# stopwatch.net
KiCad netlist of a schematic drawn in EAGLE
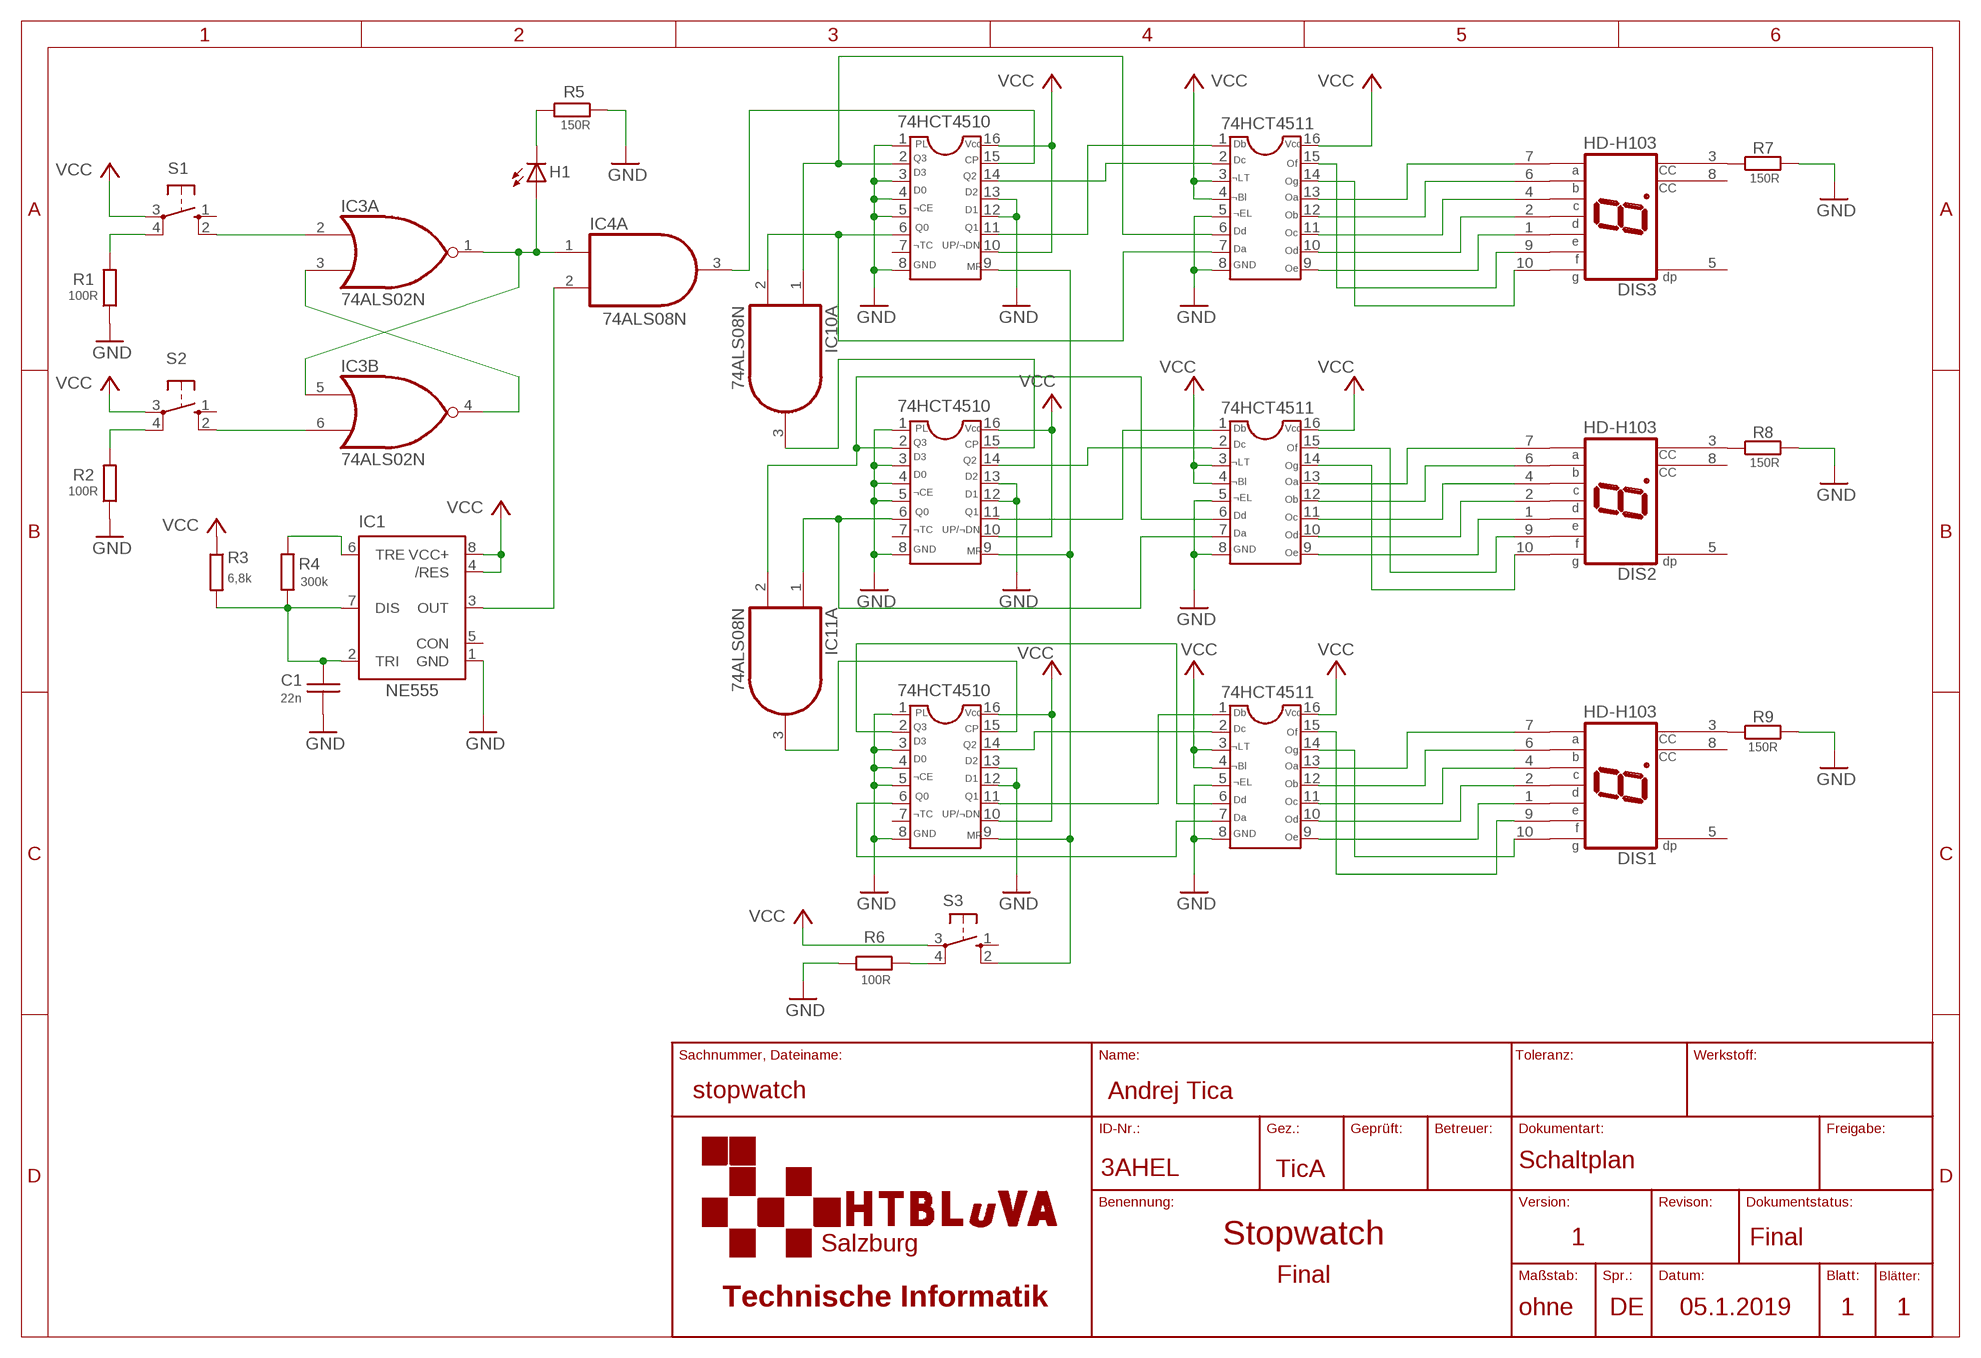
[diagram p0: schematic, sheet 1]

(export (version "E")
  (design (tool "Eeschema 10.0.6"))
  (components
    (comp (ref "C1")
      (value "22n")
      (footprint "eagle-import:C025-025X050")
      (libsource (lib "eagle-import") (part "C-V_025-025X050"))
    )
    (comp (ref "DIS1")
      (value "HD-H103")
      (footprint "eagle-import:HDSP-M")
      (libsource (lib "eagle-import") (part "HD-H103"))
    )
    (comp (ref "DIS2")
      (value "HD-H103")
      (footprint "eagle-import:HDSP-M")
      (libsource (lib "eagle-import") (part "HD-H103"))
    )
    (comp (ref "DIS3")
      (value "HD-H103")
      (footprint "eagle-import:HDSP-M")
      (libsource (lib "eagle-import") (part "HD-H103"))
    )
    (comp (ref "H1")
      (value "LED_10MM")
      (footprint "eagle-import:LED10MM")
      (libsource (lib "eagle-import") (part "LED_10MM"))
    )
    (comp (ref "IC1")
      (value "NE555")
      (footprint "eagle-import:DIL-08")
      (fields (field (name "MF") "Arrow Electronics") (field (name "MPN") "NE555N"))
      (libsource (lib "eagle-import") (part "NE555"))
    )
    (comp (ref "IC2")
      (value "74HCT4510")
      (footprint "eagle-import:DIL16")
      (libsource (lib "eagle-import") (part "ic-logik_TicA_74HCT4510"))
    )
    (comp (ref "IC3")
      (value "74ALS02N")
      (footprint "eagle-import:DIL14")
      (libsource (lib "eagle-import") (part "7402NALS"))
    )
    (comp (ref "IC4")
      (value "74ALS08N")
      (footprint "eagle-import:DIL14")
      (libsource (lib "eagle-import") (part "7408NALS"))
    )
    (comp (ref "IC5")
      (value "74HCT4510")
      (footprint "eagle-import:DIL16")
      (libsource (lib "eagle-import") (part "74HCT4510"))
    )
    (comp (ref "IC6")
      (value "74HCT4510")
      (footprint "eagle-import:DIL16")
      (libsource (lib "eagle-import") (part "ic-logik_TicA_74HCT4510"))
    )
    (comp (ref "IC7")
      (value "74HCT4510")
      (footprint "eagle-import:DIL16")
      (libsource (lib "eagle-import") (part "ic-logik_TicA_74HCT4510"))
    )
    (comp (ref "IC8")
      (value "74HCT4510")
      (footprint "eagle-import:DIL16")
      (libsource (lib "eagle-import") (part "74HCT4510"))
    )
    (comp (ref "IC9")
      (value "74HCT4510")
      (footprint "eagle-import:DIL16")
      (libsource (lib "eagle-import") (part "74HCT4510"))
    )
    (comp (ref "IC10")
      (value "74ALS08N")
      (footprint "eagle-import:DIL14")
      (fields (field (name "SPICEPREFIX") "J"))
      (libsource (lib "eagle-import") (part "7408NALS"))
    )
    (comp (ref "IC11")
      (value "74ALS08N")
      (footprint "eagle-import:DIL14")
      (fields (field (name "SPICEPREFIX") "J"))
      (libsource (lib "eagle-import") (part "7408NALS"))
    )
    (comp (ref "R1")
      (value "100R")
      (footprint "eagle-import:0204_7")
      (libsource (lib "eagle-import") (part "R-H_0204/7"))
    )
    (comp (ref "R2")
      (value "100R")
      (footprint "eagle-import:0204_7")
      (libsource (lib "eagle-import") (part "R-H_0204/7"))
    )
    (comp (ref "R3")
      (value "6,8k")
      (footprint "eagle-import:0204_7")
      (libsource (lib "eagle-import") (part "R-H_0204/7"))
    )
    (comp (ref "R4")
      (value "300k")
      (footprint "eagle-import:0204_7")
      (libsource (lib "eagle-import") (part "R-H_0204/7"))
    )
    (comp (ref "R5")
      (value "150R")
      (footprint "eagle-import:0204_7")
      (libsource (lib "eagle-import") (part "R-H_0204/7"))
    )
    (comp (ref "R6")
      (value "100R")
      (footprint "eagle-import:0204_7")
      (libsource (lib "eagle-import") (part "R-H_0204/7"))
    )
    (comp (ref "R7")
      (value "150R")
      (footprint "eagle-import:0204_7")
      (libsource (lib "eagle-import") (part "R-H_0204/7"))
    )
    (comp (ref "R8")
      (value "150R")
      (footprint "eagle-import:0204_7")
      (libsource (lib "eagle-import") (part "R-H_0204/7"))
    )
    (comp (ref "R9")
      (value "150R")
      (footprint "eagle-import:0204_7")
      (libsource (lib "eagle-import") (part "R-H_0204/7"))
    )
    (comp (ref "S1")
      (value "TASTE10-XX")
      (footprint "eagle-import:VERSTäRKER_B3F-10XX")
      (libsource (lib "eagle-import") (part "TASTE10-XX"))
    )
    (comp (ref "S2")
      (value "TASTE10-XX")
      (footprint "eagle-import:VERSTäRKER_B3F-10XX")
      (libsource (lib "eagle-import") (part "TASTE10-XX"))
    )
    (comp (ref "S3")
      (value "TASTE10-XX")
      (footprint "eagle-import:VERSTäRKER_B3F-10XX")
      (libsource (lib "eagle-import") (part "TASTE10-XX"))
    )
  )
  (nets
    (net (code "1") (name "GND") (class "Default")
      (node (ref "C1") (pin "2") (pinfunction "2_2") (pintype "passive"))
      (node (ref "IC1") (pin "1") (pinfunction "GND_1") (pintype "power_in"))
      (node (ref "IC2") (pin "1") (pinfunction "1_1") (pintype "passive"))
      (node (ref "IC2") (pin "12") (pinfunction "12_12") (pintype "passive"))
      (node (ref "IC2") (pin "13") (pinfunction "13_13") (pintype "passive"))
      (node (ref "IC2") (pin "3") (pinfunction "3_3") (pintype "passive"))
      (node (ref "IC2") (pin "4") (pinfunction "4_4") (pintype "passive"))
      (node (ref "IC2") (pin "5") (pinfunction "5_5") (pintype "passive"))
      (node (ref "IC2") (pin "8") (pinfunction "8_8") (pintype "passive"))
      (node (ref "IC5") (pin "5") (pinfunction "5_5") (pintype "passive"))
      (node (ref "IC5") (pin "8") (pinfunction "8_8") (pintype "passive"))
      (node (ref "IC6") (pin "1") (pinfunction "1_1") (pintype "passive"))
      (node (ref "IC6") (pin "12") (pinfunction "12_12") (pintype "passive"))
      (node (ref "IC6") (pin "13") (pinfunction "13_13") (pintype "passive"))
      (node (ref "IC6") (pin "3") (pinfunction "3_3") (pintype "passive"))
      (node (ref "IC6") (pin "4") (pinfunction "4_4") (pintype "passive"))
      (node (ref "IC6") (pin "5") (pinfunction "5_5") (pintype "passive"))
      (node (ref "IC6") (pin "8") (pinfunction "8_8") (pintype "passive"))
      (node (ref "IC7") (pin "1") (pinfunction "1_1") (pintype "passive"))
      (node (ref "IC7") (pin "12") (pinfunction "12_12") (pintype "passive"))
      (node (ref "IC7") (pin "13") (pinfunction "13_13") (pintype "passive"))
      (node (ref "IC7") (pin "3") (pinfunction "3_3") (pintype "passive"))
      (node (ref "IC7") (pin "4") (pinfunction "4_4") (pintype "passive"))
      (node (ref "IC7") (pin "5") (pinfunction "5_5") (pintype "passive"))
      (node (ref "IC7") (pin "8") (pinfunction "8_8") (pintype "passive"))
      (node (ref "IC8") (pin "5") (pinfunction "5_5") (pintype "passive"))
      (node (ref "IC8") (pin "8") (pinfunction "8_8") (pintype "passive"))
      (node (ref "IC9") (pin "5") (pinfunction "5_5") (pintype "passive"))
      (node (ref "IC9") (pin "8") (pinfunction "8_8") (pintype "passive"))
      (node (ref "R1") (pin "1") (pinfunction "1_1") (pintype "passive"))
      (node (ref "R2") (pin "1") (pinfunction "1_1") (pintype "passive"))
      (node (ref "R5") (pin "1") (pinfunction "1_1") (pintype "passive"))
      (node (ref "R6") (pin "1") (pinfunction "1_1") (pintype "passive"))
      (node (ref "R7") (pin "2") (pinfunction "2_2") (pintype "passive"))
      (node (ref "R8") (pin "2") (pinfunction "2_2") (pintype "passive"))
      (node (ref "R9") (pin "2") (pinfunction "2_2") (pintype "passive"))
    )
    (net (code "2") (name "Net-(DIS1-A)") (class "Default")
      (node (ref "DIS1") (pin "7") (pinfunction "A_7") (pintype "passive"))
      (node (ref "IC9") (pin "13") (pinfunction "13_13") (pintype "passive"))
    )
    (net (code "3") (name "Net-(DIS1-B)") (class "Default")
      (node (ref "DIS1") (pin "6") (pinfunction "B_6") (pintype "passive"))
      (node (ref "IC9") (pin "12") (pinfunction "12_12") (pintype "passive"))
    )
    (net (code "4") (name "Net-(DIS1-C)") (class "Default")
      (node (ref "DIS1") (pin "4") (pinfunction "C_4") (pintype "passive"))
      (node (ref "IC9") (pin "11") (pinfunction "11_11") (pintype "passive"))
    )
    (net (code "5") (name "Net-(DIS1-CC-Pad3)") (class "Default")
      (node (ref "DIS1") (pin "3") (pinfunction "CC_3") (pintype "passive"))
      (node (ref "R9") (pin "1") (pinfunction "1_1") (pintype "passive"))
    )
    (net (code "6") (name "Net-(DIS1-D)") (class "Default")
      (node (ref "DIS1") (pin "2") (pinfunction "D_2") (pintype "passive"))
      (node (ref "IC9") (pin "10") (pinfunction "10_10") (pintype "passive"))
    )
    (net (code "7") (name "Net-(DIS1-E)") (class "Default")
      (node (ref "DIS1") (pin "1") (pinfunction "E_1") (pintype "passive"))
      (node (ref "IC9") (pin "9") (pinfunction "9_9") (pintype "passive"))
    )
    (net (code "8") (name "Net-(DIS1-F)") (class "Default")
      (node (ref "DIS1") (pin "9") (pinfunction "F_9") (pintype "passive"))
      (node (ref "IC9") (pin "15") (pinfunction "15_15") (pintype "passive"))
    )
    (net (code "9") (name "Net-(DIS1-G)") (class "Default")
      (node (ref "DIS1") (pin "10") (pinfunction "G_10") (pintype "passive"))
      (node (ref "IC9") (pin "14") (pinfunction "14_14") (pintype "passive"))
    )
    (net (code "10") (name "Net-(DIS2-A)") (class "Default")
      (node (ref "DIS2") (pin "7") (pinfunction "A_7") (pintype "passive"))
      (node (ref "IC8") (pin "13") (pinfunction "13_13") (pintype "passive"))
    )
    (net (code "11") (name "Net-(DIS2-B)") (class "Default")
      (node (ref "DIS2") (pin "6") (pinfunction "B_6") (pintype "passive"))
      (node (ref "IC8") (pin "12") (pinfunction "12_12") (pintype "passive"))
    )
    (net (code "12") (name "Net-(DIS2-C)") (class "Default")
      (node (ref "DIS2") (pin "4") (pinfunction "C_4") (pintype "passive"))
      (node (ref "IC8") (pin "11") (pinfunction "11_11") (pintype "passive"))
    )
    (net (code "13") (name "Net-(DIS2-CC-Pad3)") (class "Default")
      (node (ref "DIS2") (pin "3") (pinfunction "CC_3") (pintype "passive"))
      (node (ref "R8") (pin "1") (pinfunction "1_1") (pintype "passive"))
    )
    (net (code "14") (name "Net-(DIS2-D)") (class "Default")
      (node (ref "DIS2") (pin "2") (pinfunction "D_2") (pintype "passive"))
      (node (ref "IC8") (pin "10") (pinfunction "10_10") (pintype "passive"))
    )
    (net (code "15") (name "Net-(DIS2-E)") (class "Default")
      (node (ref "DIS2") (pin "1") (pinfunction "E_1") (pintype "passive"))
      (node (ref "IC8") (pin "9") (pinfunction "9_9") (pintype "passive"))
    )
    (net (code "16") (name "Net-(DIS2-F)") (class "Default")
      (node (ref "DIS2") (pin "9") (pinfunction "F_9") (pintype "passive"))
      (node (ref "IC8") (pin "15") (pinfunction "15_15") (pintype "passive"))
    )
    (net (code "17") (name "Net-(DIS2-G)") (class "Default")
      (node (ref "DIS2") (pin "10") (pinfunction "G_10") (pintype "passive"))
      (node (ref "IC8") (pin "14") (pinfunction "14_14") (pintype "passive"))
    )
    (net (code "18") (name "Net-(DIS3-A)") (class "Default")
      (node (ref "DIS3") (pin "7") (pinfunction "A_7") (pintype "passive"))
      (node (ref "IC5") (pin "13") (pinfunction "13_13") (pintype "passive"))
    )
    (net (code "19") (name "Net-(DIS3-B)") (class "Default")
      (node (ref "DIS3") (pin "6") (pinfunction "B_6") (pintype "passive"))
      (node (ref "IC5") (pin "12") (pinfunction "12_12") (pintype "passive"))
    )
    (net (code "20") (name "Net-(DIS3-C)") (class "Default")
      (node (ref "DIS3") (pin "4") (pinfunction "C_4") (pintype "passive"))
      (node (ref "IC5") (pin "11") (pinfunction "11_11") (pintype "passive"))
    )
    (net (code "21") (name "Net-(DIS3-CC-Pad3)") (class "Default")
      (node (ref "DIS3") (pin "3") (pinfunction "CC_3") (pintype "passive"))
      (node (ref "R7") (pin "1") (pinfunction "1_1") (pintype "passive"))
    )
    (net (code "22") (name "Net-(DIS3-D)") (class "Default")
      (node (ref "DIS3") (pin "2") (pinfunction "D_2") (pintype "passive"))
      (node (ref "IC5") (pin "10") (pinfunction "10_10") (pintype "passive"))
    )
    (net (code "23") (name "Net-(DIS3-E)") (class "Default")
      (node (ref "DIS3") (pin "1") (pinfunction "E_1") (pintype "passive"))
      (node (ref "IC5") (pin "9") (pinfunction "9_9") (pintype "passive"))
    )
    (net (code "24") (name "Net-(DIS3-F)") (class "Default")
      (node (ref "DIS3") (pin "9") (pinfunction "F_9") (pintype "passive"))
      (node (ref "IC5") (pin "15") (pinfunction "15_15") (pintype "passive"))
    )
    (net (code "25") (name "Net-(DIS3-G)") (class "Default")
      (node (ref "DIS3") (pin "10") (pinfunction "G_10") (pintype "passive"))
      (node (ref "IC5") (pin "14") (pinfunction "14_14") (pintype "passive"))
    )
    (net (code "26") (name "Net-(H1-C)") (class "Default")
      (node (ref "H1") (pin "K") (pinfunction "C_K") (pintype "passive"))
      (node (ref "R5") (pin "2") (pinfunction "2_2") (pintype "passive"))
    )
    (net (code "27") (name "Net-(IC1-DIS)") (class "Default")
      (node (ref "C1") (pin "1") (pinfunction "1_1") (pintype "passive"))
      (node (ref "IC1") (pin "2") (pinfunction "TRI_2") (pintype "input"))
      (node (ref "IC1") (pin "7") (pinfunction "DIS_7") (pintype "input"))
      (node (ref "R3") (pin "2") (pinfunction "2_2") (pintype "passive"))
      (node (ref "R4") (pin "1") (pinfunction "1_1") (pintype "passive"))
    )
    (net (code "28") (name "Net-(IC1-OUT)") (class "Default")
      (node (ref "IC1") (pin "3") (pinfunction "OUT_3") (pintype "output"))
      (node (ref "IC4") (pin "2") (pinfunction "I1_2") (pintype "input"))
    )
    (net (code "29") (name "Net-(IC1-TRE)") (class "Default")
      (node (ref "IC1") (pin "6") (pinfunction "TRE_6") (pintype "input"))
      (node (ref "R4") (pin "2") (pinfunction "2_2") (pintype "passive"))
    )
    (net (code "30") (name "Net-(IC2-Pad11)") (class "Default")
      (node (ref "IC2") (pin "11") (pinfunction "11_11") (pintype "passive"))
      (node (ref "IC5") (pin "1") (pinfunction "1_1") (pintype "passive"))
    )
    (net (code "31") (name "Net-(IC2-Pad14)") (class "Default")
      (node (ref "IC2") (pin "14") (pinfunction "14_14") (pintype "passive"))
      (node (ref "IC5") (pin "2") (pinfunction "2_2") (pintype "passive"))
    )
    (net (code "32") (name "Net-(IC3A-I0)") (class "Default")
      (node (ref "IC3") (pin "2") (pinfunction "I0_2") (pintype "input"))
      (node (ref "S3") (pin "2") (pinfunction "S1_2") (pintype "passive"))
    )
    (net (code "33") (name "Net-(IC3A-I1)") (class "Default")
      (node (ref "IC3") (pin "3") (pinfunction "I1_3") (pintype "input"))
      (node (ref "IC3") (pin "4") (pinfunction "O_4") (pintype "output"))
    )
    (net (code "34") (name "Net-(IC3A-O)") (class "Default")
      (node (ref "H1") (pin "A") (pinfunction "A_A") (pintype "passive"))
      (node (ref "IC3") (pin "1") (pinfunction "O_1") (pintype "output"))
      (node (ref "IC3") (pin "5") (pinfunction "I0_5") (pintype "input"))
      (node (ref "IC4") (pin "1") (pinfunction "I0_1") (pintype "input"))
    )
    (net (code "35") (name "Net-(IC3B-I1)") (class "Default")
      (node (ref "IC3") (pin "6") (pinfunction "I1_6") (pintype "input"))
      (node (ref "S2") (pin "2") (pinfunction "S1_2") (pintype "passive"))
    )
    (net (code "36") (name "Net-(IC4A-O)") (class "Default")
      (node (ref "IC2") (pin "15") (pinfunction "15_15") (pintype "passive"))
      (node (ref "IC4") (pin "3") (pinfunction "O_3") (pintype "output"))
    )
    (net (code "37") (name "Net-(IC6-Pad11)") (class "Default")
      (node (ref "IC6") (pin "11") (pinfunction "11_11") (pintype "passive"))
      (node (ref "IC8") (pin "1") (pinfunction "1_1") (pintype "passive"))
    )
    (net (code "38") (name "Net-(IC6-Pad14)") (class "Default")
      (node (ref "IC6") (pin "14") (pinfunction "14_14") (pintype "passive"))
      (node (ref "IC8") (pin "2") (pinfunction "2_2") (pintype "passive"))
    )
    (net (code "39") (name "Net-(IC7-Pad2)") (class "Default")
      (node (ref "IC7") (pin "2") (pinfunction "2_2") (pintype "passive"))
      (node (ref "IC9") (pin "6") (pinfunction "6_6") (pintype "passive"))
    )
    (net (code "40") (name "Net-(IC7-Pad6)") (class "Default")
      (node (ref "IC7") (pin "6") (pinfunction "6_6") (pintype "passive"))
      (node (ref "IC9") (pin "7") (pinfunction "7_7") (pintype "passive"))
    )
    (net (code "41") (name "Net-(IC7-Pad11)") (class "Default")
      (node (ref "IC7") (pin "11") (pinfunction "11_11") (pintype "passive"))
      (node (ref "IC9") (pin "1") (pinfunction "1_1") (pintype "passive"))
    )
    (net (code "42") (name "Net-(IC7-Pad14)") (class "Default")
      (node (ref "IC7") (pin "14") (pinfunction "14_14") (pintype "passive"))
      (node (ref "IC9") (pin "2") (pinfunction "2_2") (pintype "passive"))
    )
    (net (code "43") (name "Net-(IC10A-I0)") (class "Default")
      (node (ref "IC10") (pin "1") (pinfunction "I0_1") (pintype "input"))
      (node (ref "IC2") (pin "2") (pinfunction "2_2") (pintype "passive"))
      (node (ref "IC5") (pin "6") (pinfunction "6_6") (pintype "passive"))
    )
    (net (code "44") (name "Net-(IC10A-I1)") (class "Default")
      (node (ref "IC10") (pin "2") (pinfunction "I1_2") (pintype "input"))
      (node (ref "IC2") (pin "6") (pinfunction "6_6") (pintype "passive"))
      (node (ref "IC5") (pin "7") (pinfunction "7_7") (pintype "passive"))
    )
    (net (code "45") (name "Net-(IC10A-O)") (class "Default")
      (node (ref "IC10") (pin "3") (pinfunction "O_3") (pintype "output"))
      (node (ref "IC6") (pin "15") (pinfunction "15_15") (pintype "passive"))
    )
    (net (code "46") (name "Net-(IC11A-I0)") (class "Default")
      (node (ref "IC11") (pin "1") (pinfunction "I0_1") (pintype "input"))
      (node (ref "IC6") (pin "6") (pinfunction "6_6") (pintype "passive"))
      (node (ref "IC8") (pin "7") (pinfunction "7_7") (pintype "passive"))
    )
    (net (code "47") (name "Net-(IC11A-I1)") (class "Default")
      (node (ref "IC11") (pin "2") (pinfunction "I1_2") (pintype "input"))
      (node (ref "IC6") (pin "2") (pinfunction "2_2") (pintype "passive"))
      (node (ref "IC8") (pin "6") (pinfunction "6_6") (pintype "passive"))
    )
    (net (code "48") (name "Net-(IC11A-O)") (class "Default")
      (node (ref "IC11") (pin "3") (pinfunction "O_3") (pintype "output"))
      (node (ref "IC7") (pin "15") (pinfunction "15_15") (pintype "passive"))
    )
    (net (code "49") (name "Net-(S1-P1)") (class "Default")
      (node (ref "R6") (pin "2") (pinfunction "2_2") (pintype "passive"))
      (node (ref "S1") (pin "4") (pinfunction "P1_4") (pintype "passive"))
    )
    (net (code "50") (name "Net-(S1-S1)") (class "Default")
      (node (ref "IC2") (pin "9") (pinfunction "9_9") (pintype "passive"))
      (node (ref "IC6") (pin "9") (pinfunction "9_9") (pintype "passive"))
      (node (ref "IC7") (pin "9") (pinfunction "9_9") (pintype "passive"))
      (node (ref "S1") (pin "2") (pinfunction "S1_2") (pintype "passive"))
    )
    (net (code "51") (name "Net-(S2-P1)") (class "Default")
      (node (ref "R2") (pin "2") (pinfunction "2_2") (pintype "passive"))
      (node (ref "S2") (pin "4") (pinfunction "P1_4") (pintype "passive"))
    )
    (net (code "52") (name "Net-(S3-P1)") (class "Default")
      (node (ref "R1") (pin "2") (pinfunction "2_2") (pintype "passive"))
      (node (ref "S3") (pin "4") (pinfunction "P1_4") (pintype "passive"))
    )
    (net (code "53") (name "VCC") (class "Default")
      (node (ref "IC1") (pin "4") (pinfunction "/RES_4") (pintype "input"))
      (node (ref "IC1") (pin "8") (pinfunction "VCC+_8") (pintype "power_in"))
      (node (ref "IC2") (pin "10") (pinfunction "10_10") (pintype "passive"))
      (node (ref "IC2") (pin "16") (pinfunction "16_16") (pintype "passive"))
      (node (ref "IC5") (pin "16") (pinfunction "16_16") (pintype "passive"))
      (node (ref "IC5") (pin "3") (pinfunction "3_3") (pintype "passive"))
      (node (ref "IC5") (pin "4") (pinfunction "4_4") (pintype "passive"))
      (node (ref "IC6") (pin "10") (pinfunction "10_10") (pintype "passive"))
      (node (ref "IC6") (pin "16") (pinfunction "16_16") (pintype "passive"))
      (node (ref "IC7") (pin "10") (pinfunction "10_10") (pintype "passive"))
      (node (ref "IC7") (pin "16") (pinfunction "16_16") (pintype "passive"))
      (node (ref "IC8") (pin "16") (pinfunction "16_16") (pintype "passive"))
      (node (ref "IC8") (pin "3") (pinfunction "3_3") (pintype "passive"))
      (node (ref "IC8") (pin "4") (pinfunction "4_4") (pintype "passive"))
      (node (ref "IC9") (pin "16") (pinfunction "16_16") (pintype "passive"))
      (node (ref "IC9") (pin "3") (pinfunction "3_3") (pintype "passive"))
      (node (ref "IC9") (pin "4") (pinfunction "4_4") (pintype "passive"))
      (node (ref "R3") (pin "1") (pinfunction "1_1") (pintype "passive"))
      (node (ref "S1") (pin "3") (pinfunction "P_3") (pintype "passive"))
      (node (ref "S2") (pin "3") (pinfunction "P_3") (pintype "passive"))
      (node (ref "S3") (pin "3") (pinfunction "P_3") (pintype "passive"))
    )
    (net (code "54") (name "unconnected-(DIS1-CC-Pad8)") (class "Default")
      (node (ref "DIS1") (pin "8") (pinfunction "CC_8") (pintype "passive"))
    )
    (net (code "55") (name "unconnected-(DIS1-DP-Pad5)") (class "Default")
      (node (ref "DIS1") (pin "5") (pinfunction "DP_5") (pintype "passive"))
    )
    (net (code "56") (name "unconnected-(DIS2-CC-Pad8)") (class "Default")
      (node (ref "DIS2") (pin "8") (pinfunction "CC_8") (pintype "passive"))
    )
    (net (code "57") (name "unconnected-(DIS2-DP-Pad5)") (class "Default")
      (node (ref "DIS2") (pin "5") (pinfunction "DP_5") (pintype "passive"))
    )
    (net (code "58") (name "unconnected-(DIS3-CC-Pad8)") (class "Default")
      (node (ref "DIS3") (pin "8") (pinfunction "CC_8") (pintype "passive"))
    )
    (net (code "59") (name "unconnected-(DIS3-DP-Pad5)") (class "Default")
      (node (ref "DIS3") (pin "5") (pinfunction "DP_5") (pintype "passive"))
    )
    (net (code "60") (name "unconnected-(IC1-CON-Pad5)") (class "Default")
      (node (ref "IC1") (pin "5") (pinfunction "CON_5") (pintype "input"))
    )
    (net (code "61") (name "unconnected-(IC2-Pad7)") (class "Default")
      (node (ref "IC2") (pin "7") (pinfunction "7_7") (pintype "passive"))
    )
    (net (code "62") (name "unconnected-(IC6-Pad7)") (class "Default")
      (node (ref "IC6") (pin "7") (pinfunction "7_7") (pintype "passive"))
    )
    (net (code "63") (name "unconnected-(IC7-Pad7)") (class "Default")
      (node (ref "IC7") (pin "7") (pinfunction "7_7") (pintype "passive"))
    )
    (net (code "64") (name "unconnected-(S1-S-Pad1)") (class "Default")
      (node (ref "S1") (pin "1") (pinfunction "S_1") (pintype "passive"))
    )
    (net (code "65") (name "unconnected-(S2-S-Pad1)") (class "Default")
      (node (ref "S2") (pin "1") (pinfunction "S_1") (pintype "passive"))
    )
    (net (code "66") (name "unconnected-(S3-S-Pad1)") (class "Default")
      (node (ref "S3") (pin "1") (pinfunction "S_1") (pintype "passive"))
    )
  )
)
